# OBDII-Ist.net
KiCad netlist of a schematic drawn in Altium Designer
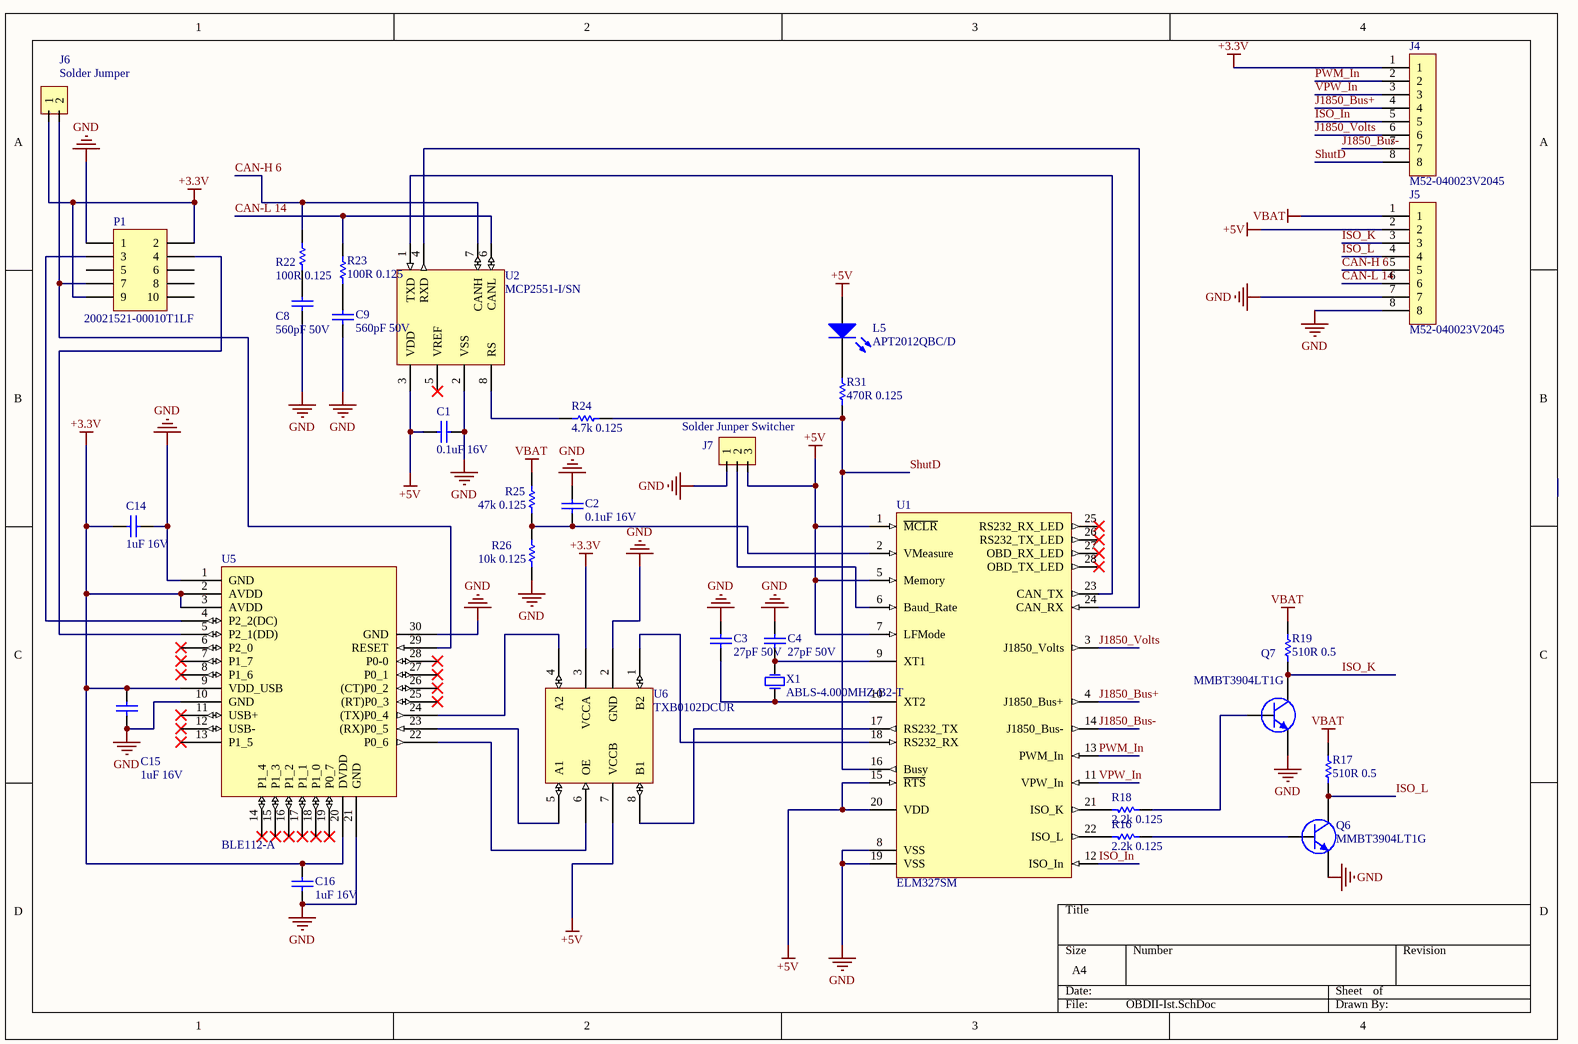
[diagram p0: OBDII-Ist.SchDoc]

(export (version "E")
  (design (tool "Eeschema 10.0.6"))
  (components
    (comp (ref "C1")
      (value "0.1uF 16V")
      (footprint "1608[0603]")
      (description "Surface-Mount Ceramic Multilayer Capacitor, 0.1uF, X5R, 10% Tolerance, 0603 Size, 16V")
      (fields (field (name "PUBLISHER") "Altium Limited"))
      (libsource (lib "OBDII-components") (part "GRM188R61C104KA01D"))
    )
    (comp (ref "C2")
      (value "0.1uF 16V")
      (footprint "1608[0603]")
      (description "Surface-Mount Ceramic Multilayer Capacitor, 0.1uF, X5R, 10% Tolerance, 0603 Size, 16V")
      (fields (field (name "PUBLISHER") "Altium Limited"))
      (libsource (lib "OBDII-components") (part "GRM188R61C104KA01D"))
    )
    (comp (ref "C3")
      (value "27pF 50V")
      (footprint "1608[0603]")
      (description "Surface-Mount Ceramic Multilayer Capacitor, 27pF, 5% Tolerance, 0603 Size, 50V")
      (fields (field (name "PUBLISHER") "Altium Limited"))
      (libsource (lib "OBDII-components") (part "CC0603JRNPO9BN270"))
    )
    (comp (ref "C4")
      (value "27pF 50V")
      (footprint "1608[0603]")
      (description "Surface-Mount Ceramic Multilayer Capacitor, 27pF, 5% Tolerance, 0603 Size, 50V")
      (fields (field (name "PUBLISHER") "Altium Limited"))
      (libsource (lib "OBDII-components") (part "CC0603JRNPO9BN270"))
    )
    (comp (ref "C8")
      (value "560pF 50V")
      (footprint "0402")
      (description "Surface-Mount Ceramic Multilayer Capacitor, 560pF, 5% Tolerance, 0402 Size, 50V")
      (fields (field (name "PUBLISHER") "Altium Limited"))
      (libsource (lib "OBDII-components") (part "C0402C561J5GACTU"))
    )
    (comp (ref "C9")
      (value "560pF 50V")
      (footprint "0402")
      (description "Surface-Mount Ceramic Multilayer Capacitor, 560pF, 5% Tolerance, 0402 Size, 50V")
      (fields (field (name "PUBLISHER") "Altium Limited"))
      (libsource (lib "OBDII-components") (part "C0402C561J5GACTU"))
    )
    (comp (ref "C14")
      (value "1uF 16V")
      (footprint "1608[0603]")
      (description "Surface-Mount Ceramic Multilayer Capacitor, 1uF, X7R, 10% Tolerance, 0603 Size, 16V")
      (libsource (lib "OBDII-components") (part "C1608X7R1C105K080AC"))
    )
    (comp (ref "C15")
      (value "1uF 16V")
      (footprint "1608[0603]")
      (description "Surface-Mount Ceramic Multilayer Capacitor, 1uF, X7R, 10% Tolerance, 0603 Size, 16V")
      (libsource (lib "OBDII-components") (part "C1608X7R1C105K080AC"))
    )
    (comp (ref "C16")
      (value "1uF 16V")
      (footprint "1608[0603]")
      (description "Surface-Mount Ceramic Multilayer Capacitor, 1uF, X7R, 10% Tolerance, 0603 Size, 16V")
      (libsource (lib "OBDII-components") (part "C1608X7R1C105K080AC"))
    )
    (comp (ref "J4")
      (value "M52-040023V2045")
      (footprint "M52-040023V2045_HOLES")
      (description "CONN HEADER .050\" 8POS PCB GOLD")
      (fields (field (name "MANUFACTURER") "Harwin"))
      (libsource (lib "OBDII-components") (part "M52-040023V2045_holes"))
    )
    (comp (ref "J5")
      (value "M52-040023V2045")
      (footprint "M52-040023V2045_HOLES")
      (description "CONN HEADER .050\" 8POS PCB GOLD")
      (fields (field (name "MANUFACTURER") "Harwin"))
      (libsource (lib "OBDII-components") (part "M52-040023V2045_holes"))
    )
    (comp (ref "J6")
      (value "Solder Jumper")
      (footprint "Solder Jumper")
      (libsource (lib "OBDII-components") (part "Solder Jumper"))
    )
    (comp (ref "J7")
      (value "Solder Junper Switcher")
      (footprint "Solder Jumper Switcher")
      (description "Solder Jumper Switcher")
      (fields (field (name "TYPE") "Solder Junper Switcher"))
      (libsource (lib "OBDII-components") (part "Solder Jumper Switcher"))
    )
    (comp (ref "L5")
      (value "APT2012QBC/D")
      (footprint "LED-0805")
      (description "Typical BLUE SiC LED")
      (libsource (lib "OBDII-components") (part "APT2012QBC/D"))
    )
    (comp (ref "P1")
      (value "20021521-00010T1LF")
      (footprint "20021521-00010T1LF")
      (description "Header, 5-Pin, Dual row,SMT SHOULDED")
      (fields (field (name "TYPE") "20021521-00010T1LF") (field (name "PUBLISHER") "Altium Limited"))
      (libsource (lib "OBDII-components") (part "20021521-00010T1LF"))
    )
    (comp (ref "Q6")
      (value "MMBT3904LT1G")
      (footprint "SOT23")
      (description "NPN 3904 General Purpose Amplifier")
      (fields
        (field (name "MANUFACTURER") "ON Semiconductor")
        (field (name "PUBLISHER") "Vanteon")
        (field (name "APPROVED") "Yes by Implemenation")
      )
      (libsource (lib "OBDII-components") (part "MMBT3904LT1G"))
    )
    (comp (ref "Q7")
      (value "MMBT3904LT1G")
      (footprint "SOT23")
      (description "NPN 3904 General Purpose Amplifier")
      (fields
        (field (name "MANUFACTURER") "ON Semiconductor")
        (field (name "PUBLISHER") "Vanteon")
        (field (name "APPROVED") "Yes by Implemenation")
      )
      (libsource (lib "OBDII-components") (part "MMBT3904LT1G"))
    )
    (comp (ref "R16")
      (value "2.2k 0.125")
      (footprint "ERA-0805")
      (description "Rectangular Thick Film Chip Resistor, 2.2 kOhm, 0.1% Tolerance, 0805 Size, 0.125 W")
      (libsource (lib "OBDII-components") (part "ERA-6AEB222V"))
    )
    (comp (ref "R17")
      (value "510R 0.5")
      (footprint "ERJ-1210")
      (description "Rectangular Thick Film Chip Resistor, 510 Ohm, 1% Tolerance, 1210 Size, 0.5 W")
      (libsource (lib "OBDII-components") (part "ERJ-14NF5100U"))
    )
    (comp (ref "R18")
      (value "2.2k 0.125")
      (footprint "ERA-0805")
      (description "Rectangular Thick Film Chip Resistor, 2.2 kOhm, 0.1% Tolerance, 0805 Size, 0.125 W")
      (libsource (lib "OBDII-components") (part "ERA-6AEB222V"))
    )
    (comp (ref "R19")
      (value "510R 0.5")
      (footprint "ERJ-1210")
      (description "Rectangular Thick Film Chip Resistor, 510 Ohm, 1% Tolerance, 1210 Size, 0.5 W")
      (libsource (lib "OBDII-components") (part "ERJ-14NF5100U"))
    )
    (comp (ref "R22")
      (value "100R 0.125")
      (footprint "ERA-0805")
      (description "Rectangular Thick Film Chip Resistor, 100 Ohm, 0.1% Tolerance, 0805 Size, 0.125 W")
      (libsource (lib "OBDII-components") (part "ERA-6AEB101V"))
    )
    (comp (ref "R23")
      (value "100R 0.125")
      (footprint "ERA-0805")
      (description "Rectangular Thick Film Chip Resistor, 100 Ohm, 0.1% Tolerance, 0805 Size, 0.125 W")
      (libsource (lib "OBDII-components") (part "ERA-6AEB101V"))
    )
    (comp (ref "R24")
      (value "4.7k 0.125")
      (footprint "ERA-0805")
      (description "Rectangular Thick Film Chip Resistor, 4.7 kOhm, 0.1% Tolerance, 0805 Size, 0.125 W")
      (libsource (lib "OBDII-components") (part "ERA-6AEB472V"))
    )
    (comp (ref "R25")
      (value "47k 0.125")
      (footprint "ERA-0805")
      (description "Rectangular Thick Film Chip Resistor, 47 kOhm, 0.1% Tolerance, 0805 Size, 0.125 W")
      (libsource (lib "OBDII-components") (part "ERA-6AEB473V"))
    )
    (comp (ref "R26")
      (value "10k 0.125")
      (footprint "ERA-0805")
      (description "Rectangular Thick Film Chip Resistor, 10 kOhm, 0.1% Tolerance, 0805 Size, 0.125 W")
      (libsource (lib "OBDII-components") (part "ERA-6AEB103V"))
    )
    (comp (ref "R31")
      (value "470R 0.125")
      (footprint "ERA-0805")
      (description "Rectangular Thick Film Chip Resistor, 470 Ohm, 0.1% Tolerance, 0805 Size, 0.125 W")
      (libsource (lib "OBDII-components") (part "ERA-6AEB471V"))
    )
    (comp (ref "U1")
      (value "ELM327SM")
      (footprint "SOIC-28N")
      (description "OBDII Interpreter IC")
      (fields (field (name "MANUFACTURER") "Elm Electronics"))
      (libsource (lib "OBDII-components") (part "ELM327_SOIC"))
    )
    (comp (ref "U2")
      (value "MCP2551-I/SN")
      (footprint "SOIC8N")
      (description "IC TRANSCEIVER CAN HI-SPD 8-SOIC")
      (fields (field (name "MANUFACTURER") "Microchip Technology"))
      (libsource (lib "OBDII-components") (part "MCP2551-I/SN"))
    )
    (comp (ref "U5")
      (value "BLE112-A")
      (footprint "BLE112-A - II")
      (description "BLE112 Bluetooth Smart Module")
      (libsource (lib "OBDII-components") (part "BLE112-A"))
    )
    (comp (ref "U6")
      (value "TXB0102DCUR")
      (footprint "TXB0102DCUR")
      (description "2-Bit Bidirectional Voltage-Level Translator with Auto Direction Sensing and +/-15-kV ESD Protect")
      (libsource (lib "OBDII-components") (part "TXB0102DCUR"))
    )
    (comp (ref "X1")
      (value "ABLS-4.000MHZ-B2-T")
      (footprint "HC-49/US")
      (description "CRYSTAL 4.000 MHZ 18PF SMD")
      (fields (field (name "MANUFACTURER") "Abracon"))
      (libsource (lib "OBDII-components") (part "ABLS-4.000MHZ-B2-T"))
    )
  )
  (nets
    (net (code "1") (name "+3.3V") (class "Default")
      (node (ref "C14") (pin "1") (pinfunction "1_1") (pintype "passive"))
      (node (ref "C15") (pin "2") (pinfunction "2_2") (pintype "passive"))
      (node (ref "C16") (pin "2") (pinfunction "2_2") (pintype "passive"))
      (node (ref "J4") (pin "1") (pinfunction "1_1") (pintype "passive"))
      (node (ref "J6") (pin "1") (pinfunction "1_1") (pintype "passive"))
      (node (ref "P1") (pin "2") (pinfunction "2_2") (pintype "passive"))
      (node (ref "P1") (pin "9") (pinfunction "9_9") (pintype "passive"))
      (node (ref "U5") (pin "2") (pinfunction "AVDD_2") (pintype "power_in"))
      (node (ref "U5") (pin "20") (pinfunction "DVDD_20") (pintype "power_in"))
      (node (ref "U5") (pin "3") (pinfunction "AVDD_3") (pintype "power_in"))
      (node (ref "U5") (pin "9") (pinfunction "VDD_USB_9") (pintype "power_in"))
      (node (ref "U6") (pin "3") (pinfunction "VCCA_3") (pintype "power_in"))
    )
    (net (code "2") (name "+5V") (class "Default")
      (node (ref "C1") (pin "1") (pinfunction "1_1") (pintype "passive"))
      (node (ref "J5") (pin "2") (pinfunction "2_2") (pintype "passive"))
      (node (ref "J7") (pin "3") (pinfunction "3_3") (pintype "passive"))
      (node (ref "L5") (pin "1") (pinfunction "A_1") (pintype "passive"))
      (node (ref "U1") (pin "1") (pinfunction "~{MCLR}_1") (pintype "input"))
      (node (ref "U1") (pin "15") (pinfunction "~{RTS}_15") (pintype "input"))
      (node (ref "U1") (pin "20") (pinfunction "VDD_20") (pintype "power_in"))
      (node (ref "U1") (pin "5") (pinfunction "Memory_5") (pintype "input"))
      (node (ref "U1") (pin "7") (pinfunction "LFMode_7") (pintype "input"))
      (node (ref "U2") (pin "3") (pinfunction "VDD_3") (pintype "power_in"))
      (node (ref "U6") (pin "7") (pinfunction "VCCB_7") (pintype "power_in"))
    )
    (net (code "3") (name "/CAN-H 6") (class "Default")
      (node (ref "J5") (pin "5") (pinfunction "5_5") (pintype "passive"))
      (node (ref "R22") (pin "2") (pinfunction "2_2") (pintype "passive"))
      (node (ref "U2") (pin "7") (pinfunction "CANH_7") (pintype "bidirectional"))
    )
    (net (code "4") (name "/CAN-L 14") (class "Default")
      (node (ref "J5") (pin "6") (pinfunction "6_6") (pintype "passive"))
      (node (ref "R23") (pin "2") (pinfunction "2_2") (pintype "passive"))
      (node (ref "U2") (pin "6") (pinfunction "CANL_6") (pintype "bidirectional"))
    )
    (net (code "5") (name "/ISO_In") (class "Default")
      (node (ref "J4") (pin "5") (pinfunction "5_5") (pintype "passive"))
      (node (ref "U1") (pin "12") (pinfunction "ISO_In_12") (pintype "input"))
    )
    (net (code "6") (name "/ISO_K") (class "Default")
      (node (ref "J5") (pin "3") (pinfunction "3_3") (pintype "passive"))
      (node (ref "Q7") (pin "3") (pinfunction "C_3") (pintype "passive"))
      (node (ref "R19") (pin "1") (pinfunction "1_1") (pintype "passive"))
    )
    (net (code "7") (name "/ISO_L") (class "Default")
      (node (ref "J5") (pin "4") (pinfunction "4_4") (pintype "passive"))
      (node (ref "Q6") (pin "3") (pinfunction "C_3") (pintype "passive"))
      (node (ref "R17") (pin "1") (pinfunction "1_1") (pintype "passive"))
    )
    (net (code "8") (name "/J1850_Bus+") (class "Default")
      (node (ref "J4") (pin "4") (pinfunction "4_4") (pintype "passive"))
      (node (ref "U1") (pin "4") (pinfunction "J1850_Bus+_4") (pintype "output"))
    )
    (net (code "9") (name "/J1850_Bus-") (class "Default")
      (node (ref "J4") (pin "7") (pinfunction "7_7") (pintype "passive"))
      (node (ref "U1") (pin "14") (pinfunction "J1850_Bus-_14") (pintype "output"))
    )
    (net (code "10") (name "/J1850_Volts") (class "Default")
      (node (ref "J4") (pin "6") (pinfunction "6_6") (pintype "passive"))
      (node (ref "U1") (pin "3") (pinfunction "J1850_Volts_3") (pintype "output"))
    )
    (net (code "11") (name "/PWM_In") (class "Default")
      (node (ref "J4") (pin "2") (pinfunction "2_2") (pintype "passive"))
      (node (ref "U1") (pin "13") (pinfunction "PWM_In_13") (pintype "input"))
    )
    (net (code "12") (name "/ShutD") (class "Default")
      (node (ref "J4") (pin "8") (pinfunction "8_8") (pintype "passive"))
      (node (ref "R24") (pin "2") (pinfunction "2_2") (pintype "passive"))
      (node (ref "R31") (pin "1") (pinfunction "1_1") (pintype "passive"))
      (node (ref "U1") (pin "16") (pinfunction "Busy_16") (pintype "output"))
    )
    (net (code "13") (name "/VPW_In") (class "Default")
      (node (ref "J4") (pin "3") (pinfunction "3_3") (pintype "passive"))
      (node (ref "U1") (pin "11") (pinfunction "VPW_In_11") (pintype "input"))
    )
    (net (code "14") (name "GND") (class "Default")
      (node (ref "C1") (pin "2") (pinfunction "2_2") (pintype "passive"))
      (node (ref "C14") (pin "2") (pinfunction "2_2") (pintype "passive"))
      (node (ref "C15") (pin "1") (pinfunction "1_1") (pintype "passive"))
      (node (ref "C16") (pin "1") (pinfunction "1_1") (pintype "passive"))
      (node (ref "C2") (pin "2") (pinfunction "2_2") (pintype "passive"))
      (node (ref "C3") (pin "2") (pinfunction "2_2") (pintype "passive"))
      (node (ref "C4") (pin "2") (pinfunction "2_2") (pintype "passive"))
      (node (ref "C8") (pin "1") (pinfunction "1_1") (pintype "passive"))
      (node (ref "C9") (pin "1") (pinfunction "1_1") (pintype "passive"))
      (node (ref "J5") (pin "7") (pinfunction "7_7") (pintype "passive"))
      (node (ref "J5") (pin "8") (pinfunction "8_8") (pintype "passive"))
      (node (ref "J7") (pin "1") (pinfunction "1_1") (pintype "passive"))
      (node (ref "P1") (pin "1") (pinfunction "1_1") (pintype "passive"))
      (node (ref "Q6") (pin "2") (pinfunction "E_2") (pintype "passive"))
      (node (ref "Q7") (pin "2") (pinfunction "E_2") (pintype "passive"))
      (node (ref "R26") (pin "1") (pinfunction "1_1") (pintype "passive"))
      (node (ref "U1") (pin "19") (pinfunction "VSS_19") (pintype "power_in"))
      (node (ref "U1") (pin "8") (pinfunction "VSS_8") (pintype "power_in"))
      (node (ref "U2") (pin "2") (pinfunction "VSS_2") (pintype "power_in"))
      (node (ref "U5") (pin "1") (pinfunction "GND_1") (pintype "power_in"))
      (node (ref "U5") (pin "10") (pinfunction "GND_10") (pintype "passive"))
      (node (ref "U5") (pin "21") (pinfunction "GND_21") (pintype "power_in"))
      (node (ref "U5") (pin "30") (pinfunction "GND_30") (pintype "power_in"))
      (node (ref "U6") (pin "2") (pinfunction "GND_2") (pintype "power_in"))
    )
    (net (code "15") (name "Net-(C8-Pad2)") (class "Default")
      (node (ref "C8") (pin "2") (pinfunction "2_2") (pintype "passive"))
      (node (ref "R22") (pin "1") (pinfunction "1_1") (pintype "passive"))
    )
    (net (code "16") (name "Net-(C9-Pad2)") (class "Default")
      (node (ref "C9") (pin "2") (pinfunction "2_2") (pintype "passive"))
      (node (ref "R23") (pin "1") (pinfunction "1_1") (pintype "passive"))
    )
    (net (code "17") (name "Net-(L5-K)") (class "Default")
      (node (ref "L5") (pin "2") (pinfunction "K_2") (pintype "passive"))
      (node (ref "R31") (pin "2") (pinfunction "2_2") (pintype "passive"))
    )
    (net (code "18") (name "Net-(Q6-B)") (class "Default")
      (node (ref "Q6") (pin "1") (pinfunction "B_1") (pintype "passive"))
      (node (ref "R16") (pin "1") (pinfunction "1_1") (pintype "passive"))
    )
    (net (code "19") (name "Net-(Q7-B)") (class "Default")
      (node (ref "Q7") (pin "1") (pinfunction "B_1") (pintype "passive"))
      (node (ref "R18") (pin "1") (pinfunction "1_1") (pintype "passive"))
    )
    (net (code "20") (name "Net-(U1-Baud_Rate)") (class "Default")
      (node (ref "J7") (pin "2") (pinfunction "2_2") (pintype "passive"))
      (node (ref "U1") (pin "6") (pinfunction "Baud_Rate_6") (pintype "input"))
    )
    (net (code "21") (name "Net-(U1-CAN_RX)") (class "Default")
      (node (ref "U1") (pin "24") (pinfunction "CAN_RX_24") (pintype "input"))
      (node (ref "U2") (pin "4") (pinfunction "RXD_4") (pintype "output"))
    )
    (net (code "22") (name "Net-(U1-CAN_TX)") (class "Default")
      (node (ref "U1") (pin "23") (pinfunction "CAN_TX_23") (pintype "output"))
      (node (ref "U2") (pin "1") (pinfunction "TXD_1") (pintype "input"))
    )
    (net (code "23") (name "Net-(U1-ISO_K)") (class "Default")
      (node (ref "R18") (pin "2") (pinfunction "2_2") (pintype "passive"))
      (node (ref "U1") (pin "21") (pinfunction "ISO_K_21") (pintype "output"))
    )
    (net (code "24") (name "Net-(U1-ISO_L)") (class "Default")
      (node (ref "R16") (pin "2") (pinfunction "2_2") (pintype "passive"))
      (node (ref "U1") (pin "22") (pinfunction "ISO_L_22") (pintype "output"))
    )
    (net (code "25") (name "Net-(U1-RS232_RX)") (class "Default")
      (node (ref "U1") (pin "18") (pinfunction "RS232_RX_18") (pintype "input"))
      (node (ref "U6") (pin "1") (pinfunction "B2_1") (pintype "bidirectional"))
    )
    (net (code "26") (name "Net-(U1-RS232_TX)") (class "Default")
      (node (ref "U1") (pin "17") (pinfunction "RS232_TX_17") (pintype "output"))
      (node (ref "U6") (pin "8") (pinfunction "B1_8") (pintype "bidirectional"))
    )
    (net (code "27") (name "Net-(U1-VMeasure)") (class "Default")
      (node (ref "C2") (pin "1") (pinfunction "1_1") (pintype "passive"))
      (node (ref "R25") (pin "1") (pinfunction "1_1") (pintype "passive"))
      (node (ref "R26") (pin "2") (pinfunction "2_2") (pintype "passive"))
      (node (ref "U1") (pin "2") (pinfunction "VMeasure_2") (pintype "input"))
    )
    (net (code "28") (name "Net-(U1-XT1)") (class "Default")
      (node (ref "C4") (pin "1") (pinfunction "1_1") (pintype "passive"))
      (node (ref "U1") (pin "9") (pinfunction "XT1_9") (pintype "passive"))
      (node (ref "X1") (pin "2") (pinfunction "OSC2_2") (pintype "passive"))
    )
    (net (code "29") (name "Net-(U1-XT2)") (class "Default")
      (node (ref "C3") (pin "1") (pinfunction "1_1") (pintype "passive"))
      (node (ref "U1") (pin "10") (pinfunction "XT2_10") (pintype "passive"))
      (node (ref "X1") (pin "1") (pinfunction "OSC1_1") (pintype "passive"))
    )
    (net (code "30") (name "Net-(U2-RS)") (class "Default")
      (node (ref "R24") (pin "1") (pinfunction "1_1") (pintype "passive"))
      (node (ref "U2") (pin "8") (pinfunction "RS_8") (pintype "passive"))
    )
    (net (code "31") (name "Net-(U5-(RX)P0_5)") (class "Default")
      (node (ref "U5") (pin "23") (pinfunction "(RX)P0_5_23") (pintype "input"))
      (node (ref "U6") (pin "5") (pinfunction "A1_5") (pintype "bidirectional"))
    )
    (net (code "32") (name "Net-(U5-(TX)P0_4)") (class "Default")
      (node (ref "U5") (pin "24") (pinfunction "(TX)P0_4_24") (pintype "output"))
      (node (ref "U6") (pin "4") (pinfunction "A2_4") (pintype "bidirectional"))
    )
    (net (code "33") (name "Net-(U5-P0_6)") (class "Default")
      (node (ref "U5") (pin "22") (pinfunction "P0_6_22") (pintype "output"))
      (node (ref "U6") (pin "6") (pinfunction "OE_6") (pintype "input"))
    )
    (net (code "34") (name "Net-(U5-P2_1(DD))") (class "Default")
      (node (ref "P1") (pin "4") (pinfunction "4_4") (pintype "passive"))
      (node (ref "U5") (pin "5") (pinfunction "P2_1(DD)_5") (pintype "bidirectional"))
    )
    (net (code "35") (name "Net-(U5-P2_2(DC))") (class "Default")
      (node (ref "P1") (pin "3") (pinfunction "3_3") (pintype "passive"))
      (node (ref "U5") (pin "4") (pinfunction "P2_2(DC)_4") (pintype "bidirectional"))
    )
    (net (code "36") (name "Net-(U5-RESET)") (class "Default")
      (node (ref "J6") (pin "2") (pinfunction "2_2") (pintype "passive"))
      (node (ref "P1") (pin "7") (pinfunction "7_7") (pintype "passive"))
      (node (ref "U5") (pin "29") (pinfunction "RESET_29") (pintype "input"))
    )
    (net (code "37") (name "VBAT") (class "Default")
      (node (ref "J5") (pin "1") (pinfunction "1_1") (pintype "passive"))
      (node (ref "R17") (pin "2") (pinfunction "2_2") (pintype "passive"))
      (node (ref "R19") (pin "2") (pinfunction "2_2") (pintype "passive"))
      (node (ref "R25") (pin "2") (pinfunction "2_2") (pintype "passive"))
    )
    (net (code "38") (name "unconnected-(P1-Pad5)") (class "Default")
      (node (ref "P1") (pin "5") (pinfunction "5_5") (pintype "passive"))
    )
    (net (code "39") (name "unconnected-(P1-Pad6)") (class "Default")
      (node (ref "P1") (pin "6") (pinfunction "6_6") (pintype "passive"))
    )
    (net (code "40") (name "unconnected-(P1-Pad8)") (class "Default")
      (node (ref "P1") (pin "8") (pinfunction "8_8") (pintype "passive"))
    )
    (net (code "41") (name "unconnected-(P1-Pad10)") (class "Default")
      (node (ref "P1") (pin "10") (pinfunction "10_10") (pintype "passive"))
    )
    (net (code "42") (name "unconnected-(U1-OBD_RX_LED-Pad27)") (class "Default")
      (node (ref "U1") (pin "27") (pinfunction "OBD_RX_LED_27") (pintype "output+no_connect"))
    )
    (net (code "43") (name "unconnected-(U1-OBD_TX_LED-Pad28)") (class "Default")
      (node (ref "U1") (pin "28") (pinfunction "OBD_TX_LED_28") (pintype "output+no_connect"))
    )
    (net (code "44") (name "unconnected-(U1-RS232_RX_LED-Pad25)") (class "Default")
      (node (ref "U1") (pin "25") (pinfunction "RS232_RX_LED_25") (pintype "output+no_connect"))
    )
    (net (code "45") (name "unconnected-(U1-RS232_TX_LED-Pad26)") (class "Default")
      (node (ref "U1") (pin "26") (pinfunction "RS232_TX_LED_26") (pintype "output+no_connect"))
    )
    (net (code "46") (name "unconnected-(U2-VREF-Pad5)") (class "Default")
      (node (ref "U2") (pin "5") (pinfunction "VREF_5") (pintype "passive+no_connect"))
    )
    (net (code "47") (name "unconnected-(U5-(CT)P0_2-Pad26)") (class "Default")
      (node (ref "U5") (pin "26") (pinfunction "(CT)P0_2_26") (pintype "bidirectional+no_connect"))
    )
    (net (code "48") (name "unconnected-(U5-(RT)P0_3-Pad25)") (class "Default")
      (node (ref "U5") (pin "25") (pinfunction "(RT)P0_3_25") (pintype "bidirectional+no_connect"))
    )
    (net (code "49") (name "unconnected-(U5-P0-0-Pad28)") (class "Default")
      (node (ref "U5") (pin "28") (pinfunction "P0-0_28") (pintype "bidirectional+no_connect"))
    )
    (net (code "50") (name "unconnected-(U5-P0_1-Pad27)") (class "Default")
      (node (ref "U5") (pin "27") (pinfunction "P0_1_27") (pintype "bidirectional+no_connect"))
    )
    (net (code "51") (name "unconnected-(U5-P0_7-Pad19)") (class "Default")
      (node (ref "U5") (pin "19") (pinfunction "P0_7_19") (pintype "bidirectional+no_connect"))
    )
    (net (code "52") (name "unconnected-(U5-P1_0-Pad18)") (class "Default")
      (node (ref "U5") (pin "18") (pinfunction "P1_0_18") (pintype "bidirectional+no_connect"))
    )
    (net (code "53") (name "unconnected-(U5-P1_1-Pad17)") (class "Default")
      (node (ref "U5") (pin "17") (pinfunction "P1_1_17") (pintype "bidirectional+no_connect"))
    )
    (net (code "54") (name "unconnected-(U5-P1_2-Pad16)") (class "Default")
      (node (ref "U5") (pin "16") (pinfunction "P1_2_16") (pintype "bidirectional+no_connect"))
    )
    (net (code "55") (name "unconnected-(U5-P1_3-Pad15)") (class "Default")
      (node (ref "U5") (pin "15") (pinfunction "P1_3_15") (pintype "bidirectional+no_connect"))
    )
    (net (code "56") (name "unconnected-(U5-P1_4-Pad14)") (class "Default")
      (node (ref "U5") (pin "14") (pinfunction "P1_4_14") (pintype "bidirectional+no_connect"))
    )
    (net (code "57") (name "unconnected-(U5-P1_5-Pad13)") (class "Default")
      (node (ref "U5") (pin "13") (pinfunction "P1_5_13") (pintype "passive+no_connect"))
    )
    (net (code "58") (name "unconnected-(U5-P1_6-Pad8)") (class "Default")
      (node (ref "U5") (pin "8") (pinfunction "P1_6_8") (pintype "bidirectional+no_connect"))
    )
    (net (code "59") (name "unconnected-(U5-P1_7-Pad7)") (class "Default")
      (node (ref "U5") (pin "7") (pinfunction "P1_7_7") (pintype "bidirectional+no_connect"))
    )
    (net (code "60") (name "unconnected-(U5-P2_0-Pad6)") (class "Default")
      (node (ref "U5") (pin "6") (pinfunction "P2_0_6") (pintype "bidirectional+no_connect"))
    )
    (net (code "61") (name "unconnected-(U5-USB+-Pad11)") (class "Default")
      (node (ref "U5") (pin "11") (pinfunction "USB+_11") (pintype "bidirectional+no_connect"))
    )
    (net (code "62") (name "unconnected-(U5-USB--Pad12)") (class "Default")
      (node (ref "U5") (pin "12") (pinfunction "USB-_12") (pintype "bidirectional+no_connect"))
    )
  )
)
